# Schema_Soldeerbout4.net
KiCad netlist of a schematic drawn in Altium Designer
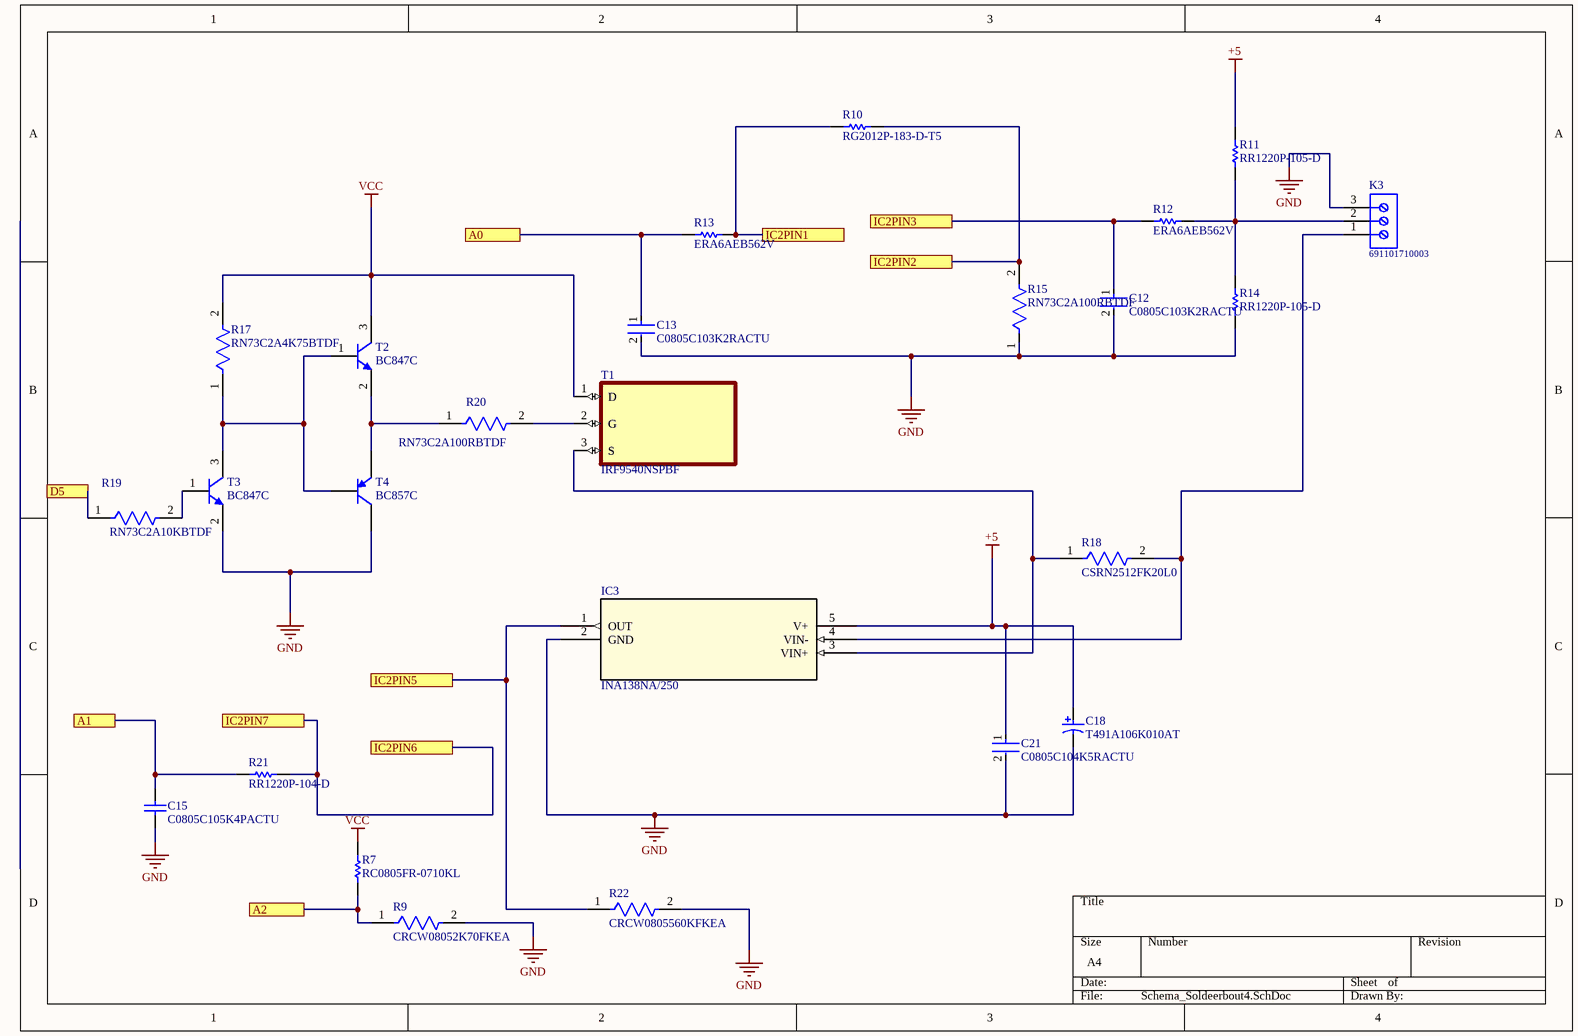
[diagram p0: Schema_Soldeerbout4.SchDoc]

(export (version "E")
  (design (tool "Eeschema 10.0.6"))
  (components
    (comp (ref "C12")
      (value "C0805C103K2RACTU")
      (footprint "FP-C0805C-DN-MFG")
      (description "CAP CER 10000PF 200V X7R 0805")
      (fields
        (field (name "OCTOPART") "https://octopart.com/c0805c103k2ractu-kemet-9138347")
        (field (name "TOLERANCE") "0.1")
      )
      (libsource (lib "Altium Content Vault") (part "b4654b650e69147ec39a6b967a45e02"))
    )
    (comp (ref "C13")
      (value "C0805C103K2RACTU")
      (footprint "FP-C0805C-DN-MFG")
      (description "CAP CER 10000PF 200V X7R 0805")
      (fields
        (field (name "OCTOPART") "https://octopart.com/c0805c103k2ractu-kemet-9138347")
        (field (name "TOLERANCE") "0.1")
      )
      (libsource (lib "Altium Content Vault") (part "b4654b650e69147ec39a6b967a45e02"))
    )
    (comp (ref "C15")
      (value "C0805C105K4PACTU")
      (footprint "CAPC2013X145X50LL20T25")
      (fields (field (name "MANUFACTURER") "Kemet"))
      (libsource (lib "Altium Content Vault") (part "CAP"))
    )
    (comp (ref "C18")
      (value "T491A106K010AT")
      (footprint "KEMT-A-3216-18-2_M")
      (description "Capacitor, Tantalum, 10 uF, +/- 10%, 10 V, -55 to 125 degC, 2-Pin SMD (1206), RoHS, Tape and Reel")
      (fields (field (name "TOLERANCE") "±10%") (field (name "MANUFACTURER") "Kemet"))
      (libsource (lib "Altium Content Vault") (part "CAP-P-2"))
    )
    (comp (ref "C21")
      (value "C0805C104K5RACTU")
      (footprint "FP-C0805C-DN-MFG")
      (description "CAP CER 0.1UF 50V X7R 0805")
      (fields
        (field (name "MANUFACTURER") "KEMET")
        (field (name "OCTOPART") "https://octopart.com/c0805c104k5ractu-kemet-143926")
      )
      (libsource (lib "Altium Content Vault") (part "b4654b650e69147ec39a6b967a45e02"))
    )
    (comp (ref "IC3")
      (value "INA138NA/250")
      (footprint "DBV5")
      (description "High-Side Measurement Current Shunt Monitor, Current Output")
      (fields
        (field (name "MANUFACTURER") "Texas Instruments")
        (field (name "GENERIC_PART_NUMBER") "INA138")
        (field (name "COPYRIGHT") "Copyright (C) 2018 Accelerated Designs. All rights reserved")
      )
      (libsource (lib "2021-03-03_13-19-46") (part "INA138NA/250"))
    )
    (comp (ref "K3")
      (value "691101710003")
      (footprint "691101710003")
      (description "Series 101 - 5.00 mm Horizontal Entry Modular with Pressure Clamp WR-TBL, 3 pin")
      (fields (field (name "MANUFACTURER") "Wurth Elektronik") (field (name "PUBLISHER") "WurthElektronik"))
      (libsource (lib "Altium Content Vault") (part "WE-CN-1P-F-TB3"))
    )
    (comp (ref "R7")
      (value "RC0805FR-0710KL")
      (footprint "RESC2013X60X35NL10T20")
      (description "Chip Resistor, 10 KOhm, +/- 1%, 0.125 W, -55 to 155 degC, 0805 (2012 Metric), RoHS, Tape and Reel")
      (fields (field (name "MANUFACTURER") "Yageo"))
      (libsource (lib "Altium Content Vault") (part "RES-2"))
    )
    (comp (ref "R9")
      (value "CRCW08052K70FKEA")
      (footprint "FP-CRCW0805-e3-IPC_C")
      (description "RES Thick Film, 2.7kΩ, 1%, 0.125W, 100ppm/°C, 0805")
      (fields (field (name "TOLERANCE") "1%"))
      (libsource (lib "Altium Content Vault") (part "1029c3af85768c4190bb7ad29bc67b5"))
    )
    (comp (ref "R10")
      (value "RG2012P-183-D-T5")
      (footprint "RESC2013X50X40LL20T20")
      (fields (field (name "MANUFACTURER") "Susumu"))
      (libsource (lib "Altium Content Vault") (part "RES"))
    )
    (comp (ref "R11")
      (value "RR1220P-105-D")
      (footprint "RESC2013X50X40ML20T20")
      (fields (field (name "MANUFACTURER") "Susumu"))
      (libsource (lib "Altium Content Vault") (part "RES"))
    )
    (comp (ref "R12")
      (value "ERA6AEB562V")
      (footprint "RESC2013X60X40ML20T25")
      (fields (field (name "MANUFACTURER") "Panasonic"))
      (libsource (lib "Altium Content Vault") (part "RES"))
    )
    (comp (ref "R13")
      (value "ERA6AEB562V")
      (footprint "RESC2013X60X40ML20T25")
      (fields (field (name "MANUFACTURER") "Panasonic"))
      (libsource (lib "Altium Content Vault") (part "RES"))
    )
    (comp (ref "R14")
      (value "RR1220P-105-D")
      (footprint "RESC2013X50X40ML20T20")
      (fields (field (name "MANUFACTURER") "Susumu"))
      (libsource (lib "Altium Content Vault") (part "RES"))
    )
    (comp (ref "R15")
      (value "RN73C2A100RBTDF")
      (footprint "FP-RN732A-MFG")
      (description "SMD Chip Resistor, Thin Film, 100Ω, 100 V, 0805 [2012 Metric], 100 mW, 0.1%, RN73 Series")
      (fields
        (field (name "OCTOPART") "https://octopart.com/rn73c2a100rbtdf-te+connectivity-41188433")
        (field (name "TOLERANCE") "0.1%")
      )
      (libsource (lib "Altium Content Vault") (part "1029c3af85768c4190bb7ad29bc67b5"))
    )
    (comp (ref "R17")
      (value "RN73C2A4K75BTDF")
      (footprint "FP-RN732A-MFG")
      (description "SMD Chip Resistor, Thin Film, 4.75KΩ, 100 V, 0805 [2012 Metric], 100 mW, 0.1%, RN73 Series")
      (fields (field (name "TOLERANCE") "0.1%") (field (name "MANUFACTURER") "TE Connectivity"))
      (libsource (lib "Altium Content Vault") (part "1029c3af85768c4190bb7ad29bc67b5"))
    )
    (comp (ref "R18")
      (value "CSRN2512FK20L0")
      (footprint "FP-CSRN2512-IPC_C")
      (description "Res Thick Film 2512 20mΩ 1% 2W ±200ppm/°C Molded SMD Plastic T/R")
      (fields (field (name "TOLERANCE") "1%"))
      (libsource (lib "Altium Content Vault") (part "1029c3af85768c4190bb7ad29bc67b5"))
    )
    (comp (ref "R19")
      (value "RN73C2A10KBTDF")
      (footprint "FP-RN732A-MFG")
      (description "SMD Chip Resistor, Thin Film, 10KΩ, 100 V, 0805 [2012 Metric], 100 mW, 0.1%, RN73 Series")
      (fields
        (field (name "OCTOPART") "https://octopart.com/rn73c2a10kbtdf-te+connectivity-21400356")
        (field (name "MANUFACTURER") "TE Connectivity")
      )
      (libsource (lib "Altium Content Vault") (part "1029c3af85768c4190bb7ad29bc67b5"))
    )
    (comp (ref "R20")
      (value "RN73C2A100RBTDF")
      (footprint "FP-RN732A-MFG")
      (description "SMD Chip Resistor, Thin Film, 100Ω, 100 V, 0805 [2012 Metric], 100 mW, 0.1%, RN73 Series")
      (fields
        (field (name "OCTOPART") "https://octopart.com/rn73c2a100rbtdf-te+connectivity-41188433")
        (field (name "TOLERANCE") "0.1%")
      )
      (libsource (lib "Altium Content Vault") (part "1029c3af85768c4190bb7ad29bc67b5"))
    )
    (comp (ref "R21")
      (value "RR1220P-104-D")
      (footprint "RESC2013X50X40LL20T20")
      (fields (field (name "MANUFACTURER") "Susumu"))
      (libsource (lib "Altium Content Vault") (part "RES"))
    )
    (comp (ref "R22")
      (value "CRCW0805560KFKEA")
      (footprint "FP-CRCW0805-e3-IPC_A")
      (description "RES Thick Film, 560kΩ, 1%, 0.125W, 100ppm/°C, 0805")
      (fields (field (name "TOLERANCE") "1%"))
      (libsource (lib "Altium Content Vault") (part "1029c3af85768c4190bb7ad29bc67b5"))
    )
    (comp (ref "T1")
      (value "IRF9540NSPBF")
      (footprint "DPAK508P1524X483-3N")
      (fields (field (name "MF") "Infineon"))
      (libsource (lib "IRF9540NSPBF") (part "IRF9540NSPBF"))
    )
    (comp (ref "T2")
      (value "BC847C")
      (footprint "INF-SOT23_L")
      (description "NPN Silicon AF Transistor, 45 V VCEO, 100 mA IC, SOT23, Reel, Green")
      (fields (field (name "MANUFACTURER") "Infineon"))
      (libsource (lib "Altium Content Vault") (part "INF-BJTNPN-BEC-3"))
    )
    (comp (ref "T3")
      (value "BC847C")
      (footprint "INF-SOT23_L")
      (description "NPN Silicon AF Transistor, 45 V VCEO, 100 mA IC, SOT23, Reel, Green")
      (fields (field (name "MANUFACTURER") "Infineon"))
      (libsource (lib "Altium Content Vault") (part "INF-BJTNPN-BEC-3"))
    )
    (comp (ref "T4")
      (value "BC857C")
      (footprint "INF-SOT23_N")
      (description "PNP Silicon AF Transistor, 45 V VCEO, 100 mA IC, SOT23, Reel, Green")
      (fields (field (name "MANUFACTURER") "Infineon"))
      (libsource (lib "Altium Content Vault") (part "INF-BJTPNP-BEC-3"))
    )
  )
  (nets
    (net (code "1") (name "+5") (class "Default")
      (node (ref "C18") (pin "1") (pinfunction "1_1") (pintype "passive"))
      (node (ref "C21") (pin "1") (pinfunction "1_1") (pintype "passive"))
      (node (ref "IC3") (pin "5") (pinfunction "V+_5") (pintype "power_in"))
      (node (ref "R11") (pin "2") (pinfunction "2_2") (pintype "passive"))
    )
    (net (code "2") (name "/A0") (class "Default")
      (node (ref "C13") (pin "1") (pinfunction "1_1") (pintype "passive"))
      (node (ref "R13") (pin "1") (pinfunction "1_1") (pintype "passive"))
    )
    (net (code "3") (name "/A1") (class "Default")
      (node (ref "C15") (pin "2") (pinfunction "2_2") (pintype "passive"))
      (node (ref "R21") (pin "1") (pinfunction "1_1") (pintype "passive"))
    )
    (net (code "4") (name "/A2") (class "Default")
      (node (ref "R7") (pin "1") (pinfunction "1_1") (pintype "passive"))
      (node (ref "R9") (pin "1") (pinfunction "1_1") (pintype "passive"))
    )
    (net (code "5") (name "/D5") (class "Default")
      (node (ref "R19") (pin "1") (pinfunction "1_1") (pintype "passive"))
    )
    (net (code "6") (name "/IC2PIN1") (class "Default")
      (node (ref "R10") (pin "1") (pinfunction "1_1") (pintype "passive"))
      (node (ref "R13") (pin "2") (pinfunction "2_2") (pintype "passive"))
    )
    (net (code "7") (name "/IC2PIN2") (class "Default")
      (node (ref "R10") (pin "2") (pinfunction "2_2") (pintype "passive"))
      (node (ref "R15") (pin "2") (pinfunction "2_2") (pintype "passive"))
    )
    (net (code "8") (name "/IC2PIN3") (class "Default")
      (node (ref "C12") (pin "1") (pinfunction "1_1") (pintype "passive"))
      (node (ref "R12") (pin "1") (pinfunction "1_1") (pintype "passive"))
    )
    (net (code "9") (name "/IC2PIN5") (class "Default")
      (node (ref "IC3") (pin "1") (pinfunction "OUT_1") (pintype "output"))
      (node (ref "R22") (pin "1") (pinfunction "1_1") (pintype "passive"))
    )
    (net (code "10") (name "/IC2PIN6") (class "Default")
      (node (ref "R21") (pin "2") (pinfunction "2_2") (pintype "passive"))
    )
    (net (code "11") (name "GND") (class "Default")
      (node (ref "C12") (pin "2") (pinfunction "2_2") (pintype "passive"))
      (node (ref "C13") (pin "2") (pinfunction "2_2") (pintype "passive"))
      (node (ref "C15") (pin "1") (pinfunction "1_1") (pintype "passive"))
      (node (ref "C18") (pin "2") (pinfunction "2_2") (pintype "passive"))
      (node (ref "C21") (pin "2") (pinfunction "2_2") (pintype "passive"))
      (node (ref "IC3") (pin "2") (pinfunction "GND_2") (pintype "power_in"))
      (node (ref "K3") (pin "3") (pinfunction "3_3") (pintype "passive"))
      (node (ref "R14") (pin "1") (pinfunction "1_1") (pintype "passive"))
      (node (ref "R15") (pin "1") (pinfunction "1_1") (pintype "passive"))
      (node (ref "R22") (pin "2") (pinfunction "2_2") (pintype "passive"))
      (node (ref "R9") (pin "2") (pinfunction "2_2") (pintype "passive"))
      (node (ref "T3") (pin "2") (pinfunction "E_2") (pintype "passive"))
      (node (ref "T4") (pin "3") (pinfunction "C_3") (pintype "passive"))
    )
    (net (code "12") (name "Net-(IC3-VIN+)") (class "Default")
      (node (ref "IC3") (pin "3") (pinfunction "VIN+_3") (pintype "input"))
      (node (ref "R18") (pin "1") (pinfunction "1_1") (pintype "passive"))
      (node (ref "T1") (pin "3") (pinfunction "S_3") (pintype "bidirectional"))
    )
    (net (code "13") (name "Net-(IC3-VIN-)") (class "Default")
      (node (ref "IC3") (pin "4") (pinfunction "VIN-_4") (pintype "input"))
      (node (ref "K3") (pin "1") (pinfunction "1_1") (pintype "passive"))
      (node (ref "R18") (pin "2") (pinfunction "2_2") (pintype "passive"))
    )
    (net (code "14") (name "Net-(K3-Pad2)") (class "Default")
      (node (ref "K3") (pin "2") (pinfunction "2_2") (pintype "passive"))
      (node (ref "R11") (pin "1") (pinfunction "1_1") (pintype "passive"))
      (node (ref "R12") (pin "2") (pinfunction "2_2") (pintype "passive"))
      (node (ref "R14") (pin "2") (pinfunction "2_2") (pintype "passive"))
    )
    (net (code "15") (name "Net-(T1-G)") (class "Default")
      (node (ref "R20") (pin "2") (pinfunction "2_2") (pintype "passive"))
      (node (ref "T1") (pin "2") (pinfunction "G_2") (pintype "bidirectional"))
    )
    (net (code "16") (name "Net-(T2-B)") (class "Default")
      (node (ref "R17") (pin "1") (pinfunction "1_1") (pintype "passive"))
      (node (ref "T2") (pin "1") (pinfunction "B_1") (pintype "passive"))
      (node (ref "T3") (pin "3") (pinfunction "C_3") (pintype "passive"))
      (node (ref "T4") (pin "1") (pinfunction "B_1") (pintype "passive"))
    )
    (net (code "17") (name "Net-(T2-E)") (class "Default")
      (node (ref "R20") (pin "1") (pinfunction "1_1") (pintype "passive"))
      (node (ref "T2") (pin "2") (pinfunction "E_2") (pintype "passive"))
      (node (ref "T4") (pin "2") (pinfunction "E_2") (pintype "passive"))
    )
    (net (code "18") (name "Net-(T3-B)") (class "Default")
      (node (ref "R19") (pin "2") (pinfunction "2_2") (pintype "passive"))
      (node (ref "T3") (pin "1") (pinfunction "B_1") (pintype "passive"))
    )
    (net (code "19") (name "VCC") (class "Default")
      (node (ref "R17") (pin "2") (pinfunction "2_2") (pintype "passive"))
      (node (ref "R7") (pin "2") (pinfunction "2_2") (pintype "passive"))
      (node (ref "T1") (pin "1") (pinfunction "D_1") (pintype "bidirectional"))
      (node (ref "T2") (pin "3") (pinfunction "C_3") (pintype "passive"))
    )
  )
)
